# Potenciometro.net
KiCad netlist of a schematic drawn in EAGLE
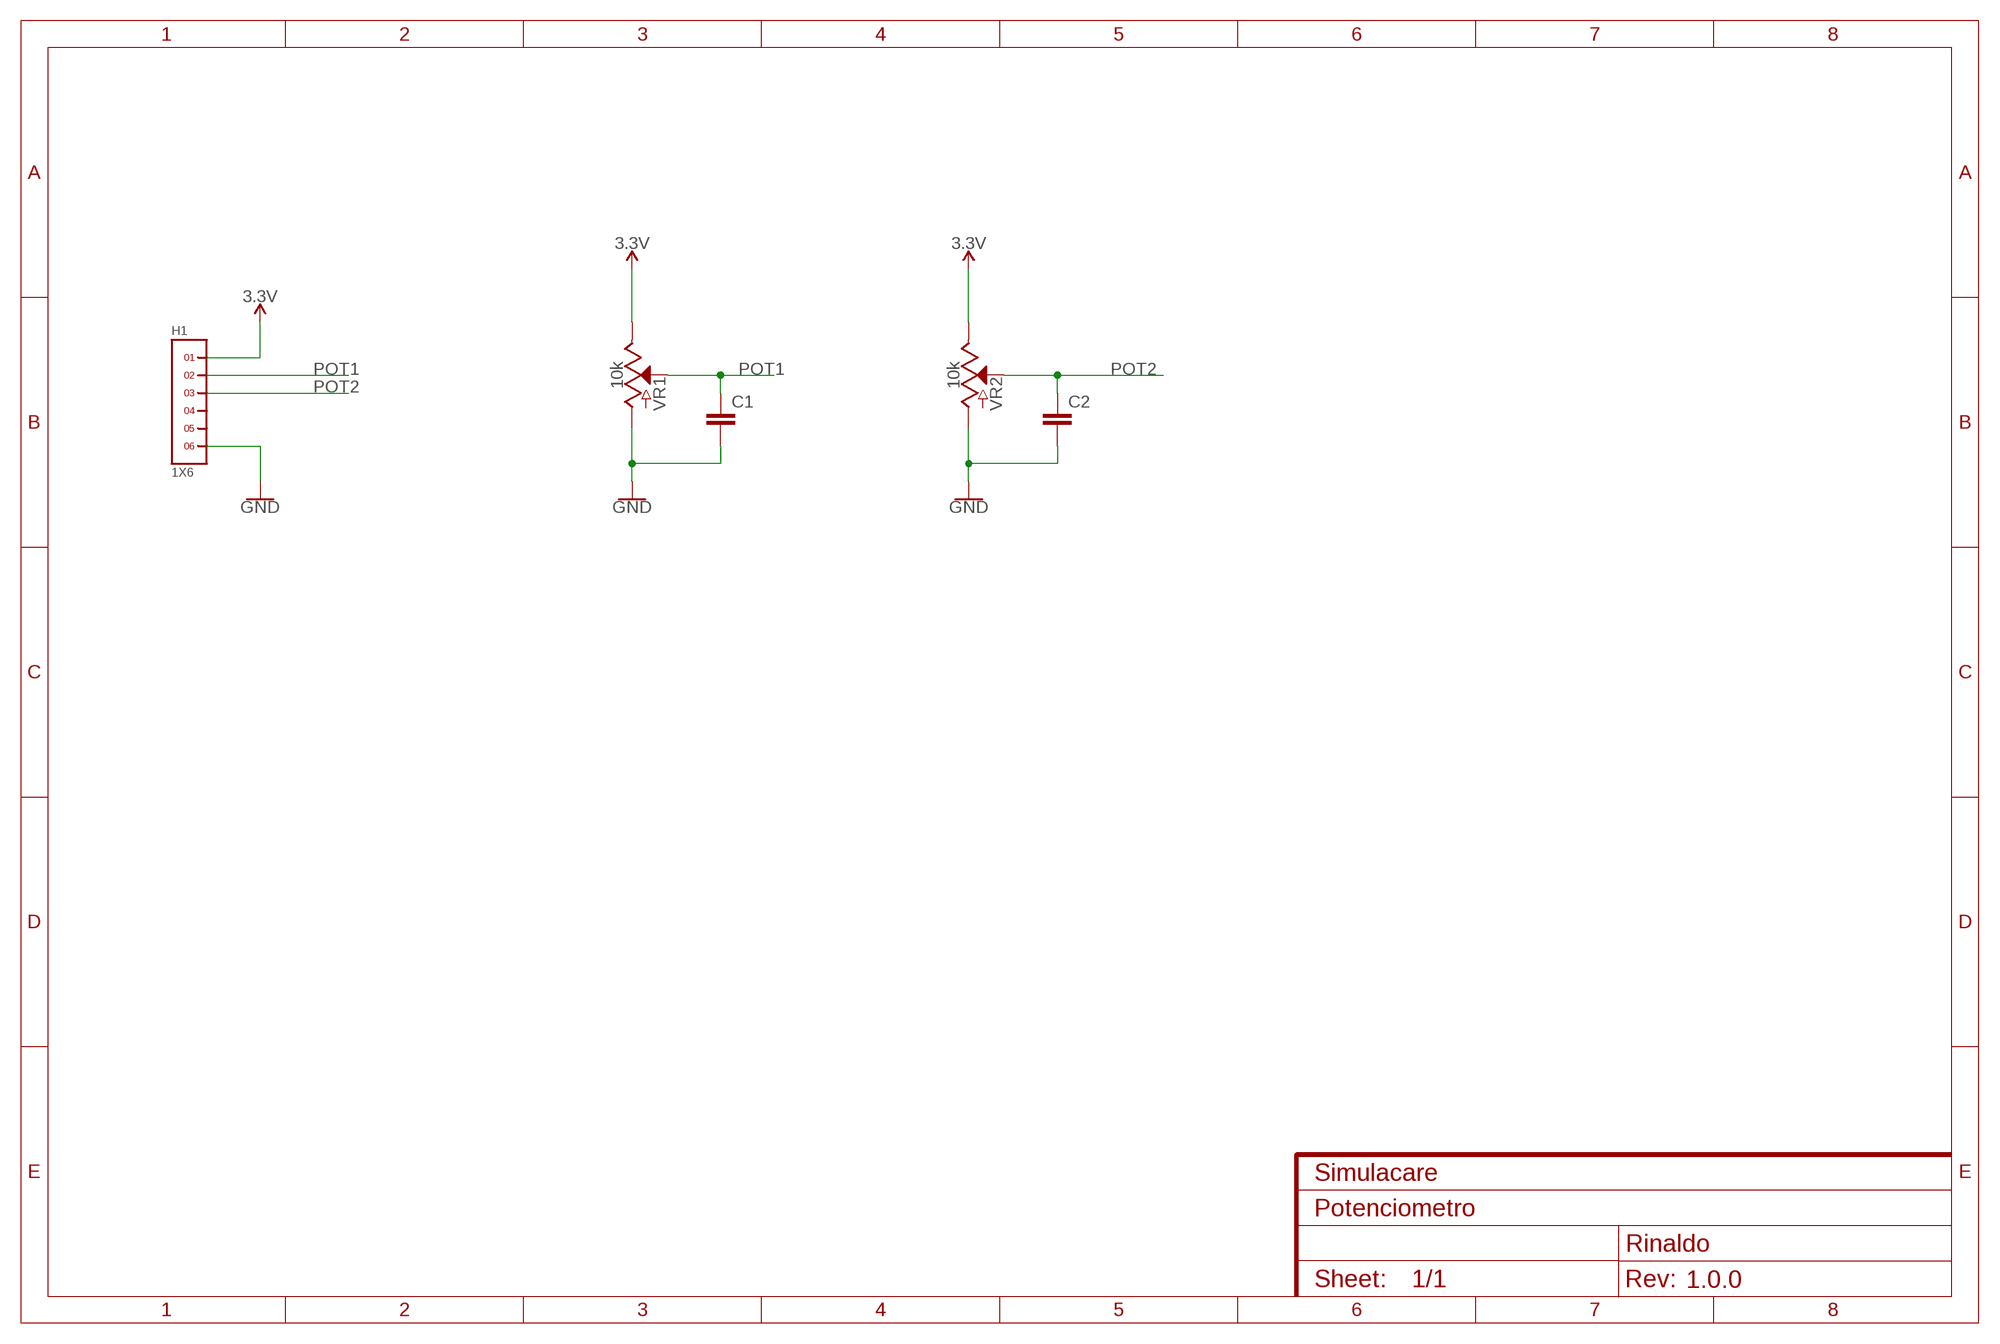
[diagram p0: schematic, sheet 1]

(export (version "E")
  (design (tool "Eeschema 10.0.6"))
  (components
    (comp (ref "C1")
      (value "C-EUC0603")
      (footprint "eagle-import:C0603")
      (libsource (lib "eagle-import") (part "C-EUC0603"))
    )
    (comp (ref "C2")
      (value "C-EUC0603")
      (footprint "eagle-import:C0603")
      (libsource (lib "eagle-import") (part "C-EUC0603"))
    )
    (comp (ref "H1")
      (value "1X6")
      (footprint "eagle-import:1X6")
      (libsource (lib "eagle-import") (part "1X6"))
    )
    (comp (ref "VR1")
      (value "10k")
      (footprint "eagle-import:SLIDER-MEDIUM")
      (libsource (lib "eagle-import") (part "POTENTIOMETER_SLIDE-30MM-1/10W-20%"))
    )
    (comp (ref "VR2")
      (value "10k")
      (footprint "eagle-import:SLIDER-MEDIUM")
      (libsource (lib "eagle-import") (part "POTENTIOMETER_SLIDE-30MM-1/10W-20%"))
    )
  )
  (nets
    (net (code "1") (name "/POT1") (class "Default")
      (node (ref "C1") (pin "1") (pinfunction "1_1") (pintype "passive"))
      (node (ref "H1") (pin "2") (pinfunction "2_2") (pintype "bidirectional"))
      (node (ref "VR1") (pin "WIPER") (pinfunction "S_WIPER") (pintype "passive"))
    )
    (net (code "2") (name "/POT2") (class "Default")
      (node (ref "C2") (pin "1") (pinfunction "1_1") (pintype "passive"))
      (node (ref "H1") (pin "3") (pinfunction "3_3") (pintype "bidirectional"))
      (node (ref "VR2") (pin "WIPER") (pinfunction "S_WIPER") (pintype "passive"))
    )
    (net (code "3") (name "3.3V") (class "Default")
      (node (ref "H1") (pin "1") (pinfunction "1_1") (pintype "bidirectional"))
      (node (ref "VR1") (pin "TOP") (pinfunction "E_TOP") (pintype "passive"))
      (node (ref "VR2") (pin "TOP") (pinfunction "E_TOP") (pintype "passive"))
    )
    (net (code "4") (name "GND") (class "Default")
      (node (ref "C1") (pin "2") (pinfunction "2_2") (pintype "passive"))
      (node (ref "C2") (pin "2") (pinfunction "2_2") (pintype "passive"))
      (node (ref "H1") (pin "6") (pinfunction "6_6") (pintype "bidirectional"))
      (node (ref "VR1") (pin "BOTTOM") (pinfunction "A_BOTTOM") (pintype "passive"))
      (node (ref "VR2") (pin "BOTTOM") (pinfunction "A_BOTTOM") (pintype "passive"))
    )
    (net (code "5") (name "unconnected-(H1-Pad4)") (class "Default")
      (node (ref "H1") (pin "4") (pinfunction "4_4") (pintype "bidirectional"))
    )
    (net (code "6") (name "unconnected-(H1-Pad5)") (class "Default")
      (node (ref "H1") (pin "5") (pinfunction "5_5") (pintype "bidirectional"))
    )
  )
)
